# working.net
KiCad netlist of a schematic drawn in EAGLE
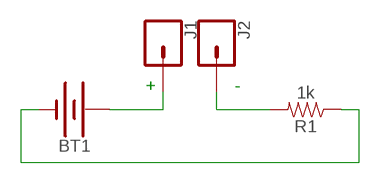
[diagram p0: schematic, sheet 1]

(export (version "E")
  (design (tool "Eeschema 10.0.6"))
  (components
    (comp (ref "BT1")
      (value "BATTERY-20MM_SMD_4LEGS")
      (footprint "eagle-import:BATTCON_20MM_4LEGS")
      (libsource (lib "eagle-import") (part "BATTERY-20MM_SMD_4LEGS"))
    )
    (comp (ref "J1")
      (value "CONN_01")
      (footprint "eagle-import:1X01")
      (libsource (lib "eagle-import") (part "CONN_01"))
    )
    (comp (ref "J2")
      (value "CONN_01")
      (footprint "eagle-import:1X01")
      (libsource (lib "eagle-import") (part "CONN_01"))
    )
    (comp (ref "R1")
      (value "1k")
      (footprint "eagle-import:AXIAL-0.3")
      (libsource (lib "eagle-import") (part "1KOHM-HORIZ-1/4W-1%"))
    )
  )
  (nets
    (net (code "1") (name "Net-(BT1-+-PadPOSITIVE@1)") (class "Default")
      (node (ref "BT1") (pin "POSITIVE@1") (pinfunction "+_POSITIVE@1") (pintype "power_in"))
      (node (ref "BT1") (pin "POSITIVE@2") (pinfunction "+_POSITIVE@2") (pintype "power_in"))
      (node (ref "BT1") (pin "POSITIVE@3") (pinfunction "+_POSITIVE@3") (pintype "power_in"))
      (node (ref "BT1") (pin "POSITIVE@4") (pinfunction "+_POSITIVE@4") (pintype "power_in"))
      (node (ref "J1") (pin "1") (pinfunction "1_1") (pintype "passive"))
    )
    (net (code "2") (name "Net-(BT1--)") (class "Default")
      (node (ref "BT1") (pin "NEGATIVE") (pinfunction "-_NEGATIVE") (pintype "power_in"))
      (node (ref "R1") (pin "P$1") (pinfunction "1_P$1") (pintype "passive"))
    )
    (net (code "3") (name "Net-(R1-2)") (class "Default")
      (node (ref "J2") (pin "1") (pinfunction "1_1") (pintype "passive"))
      (node (ref "R1") (pin "P$2") (pinfunction "2_P$2") (pintype "passive"))
    )
  )
)
